# AutoTunerV2.net
KiCad netlist of a schematic drawn in EAGLE
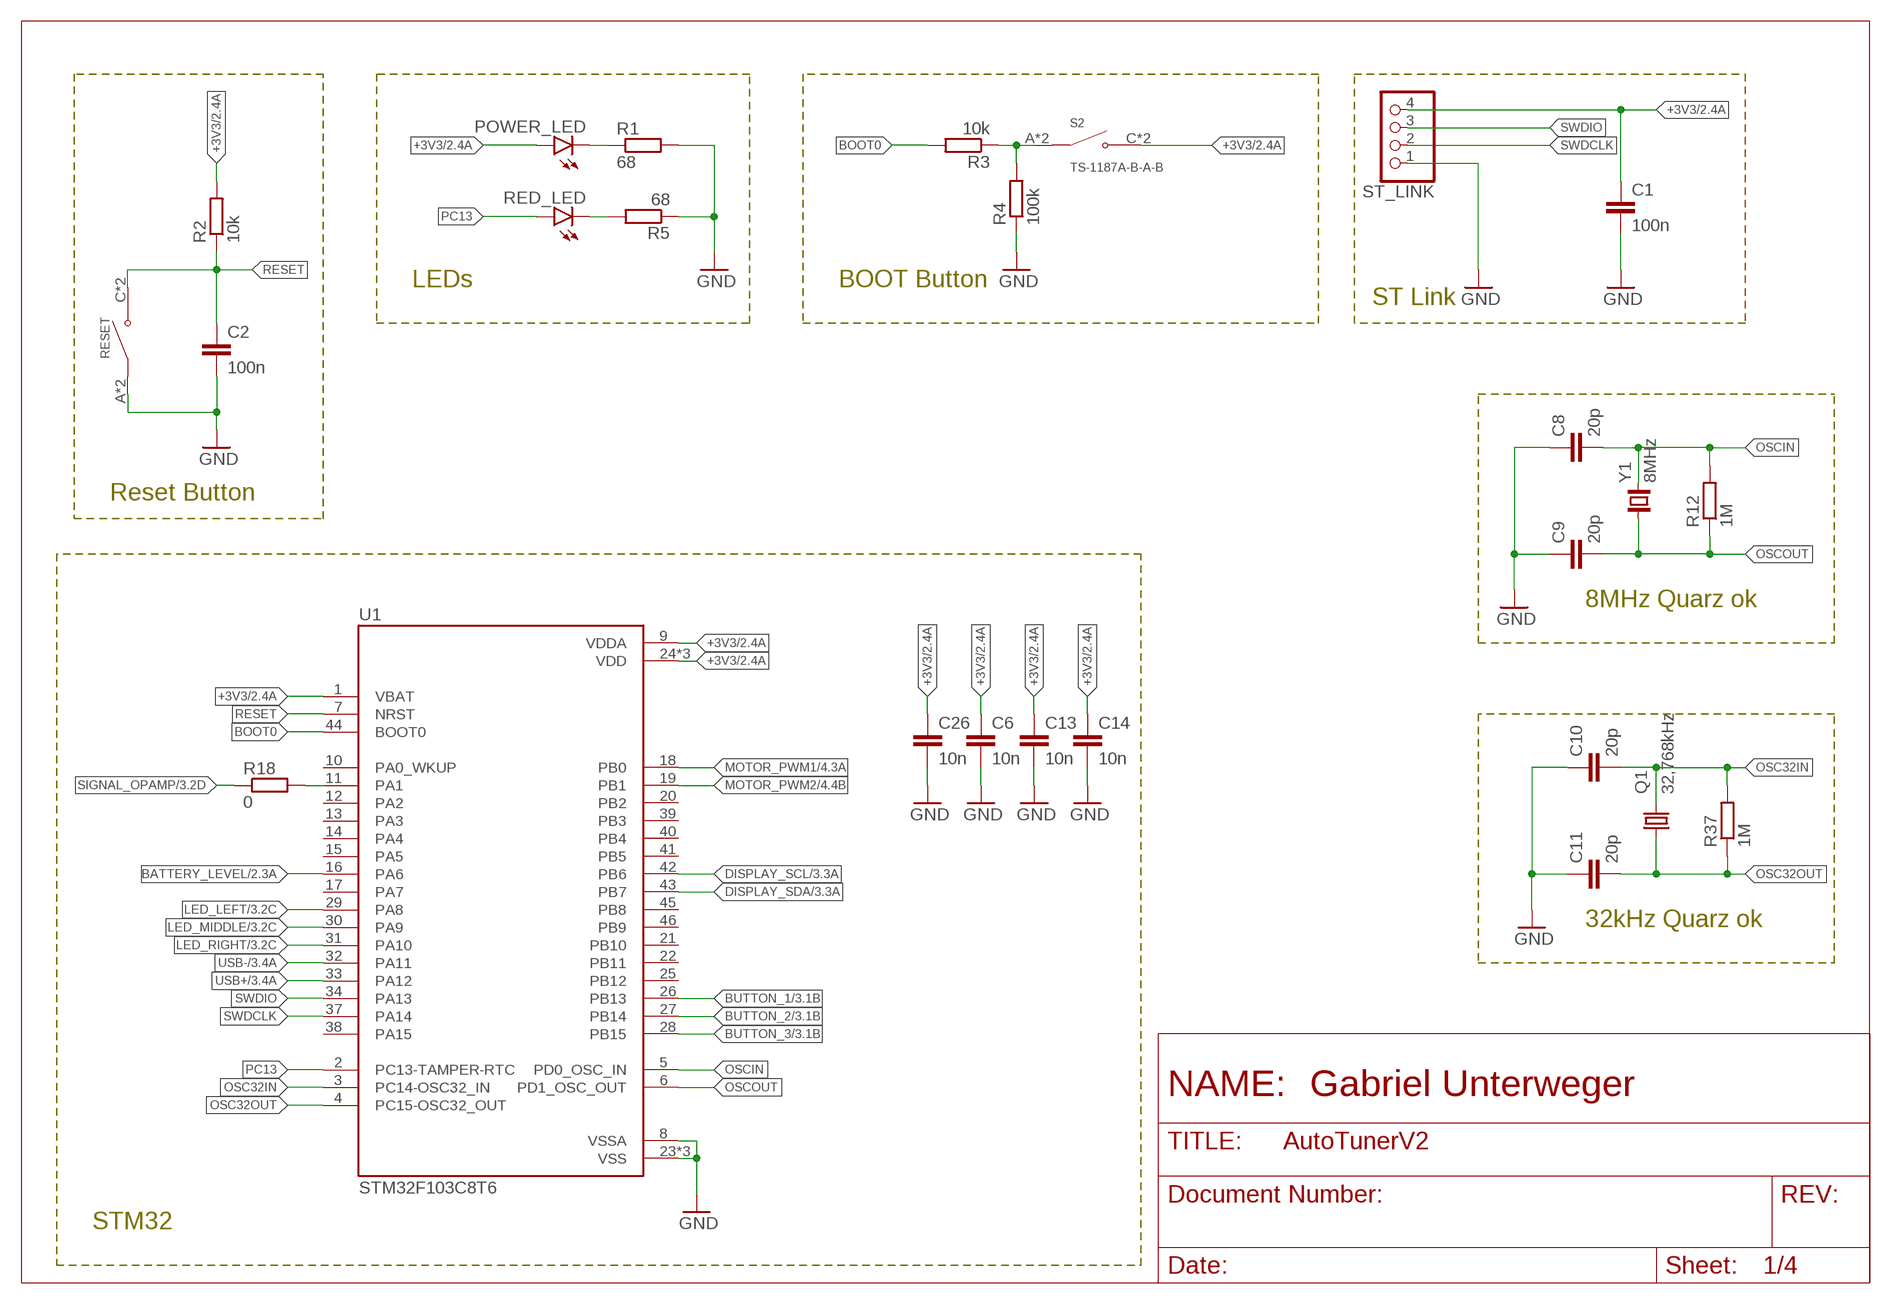
[diagram p0: schematic, sheet 1]
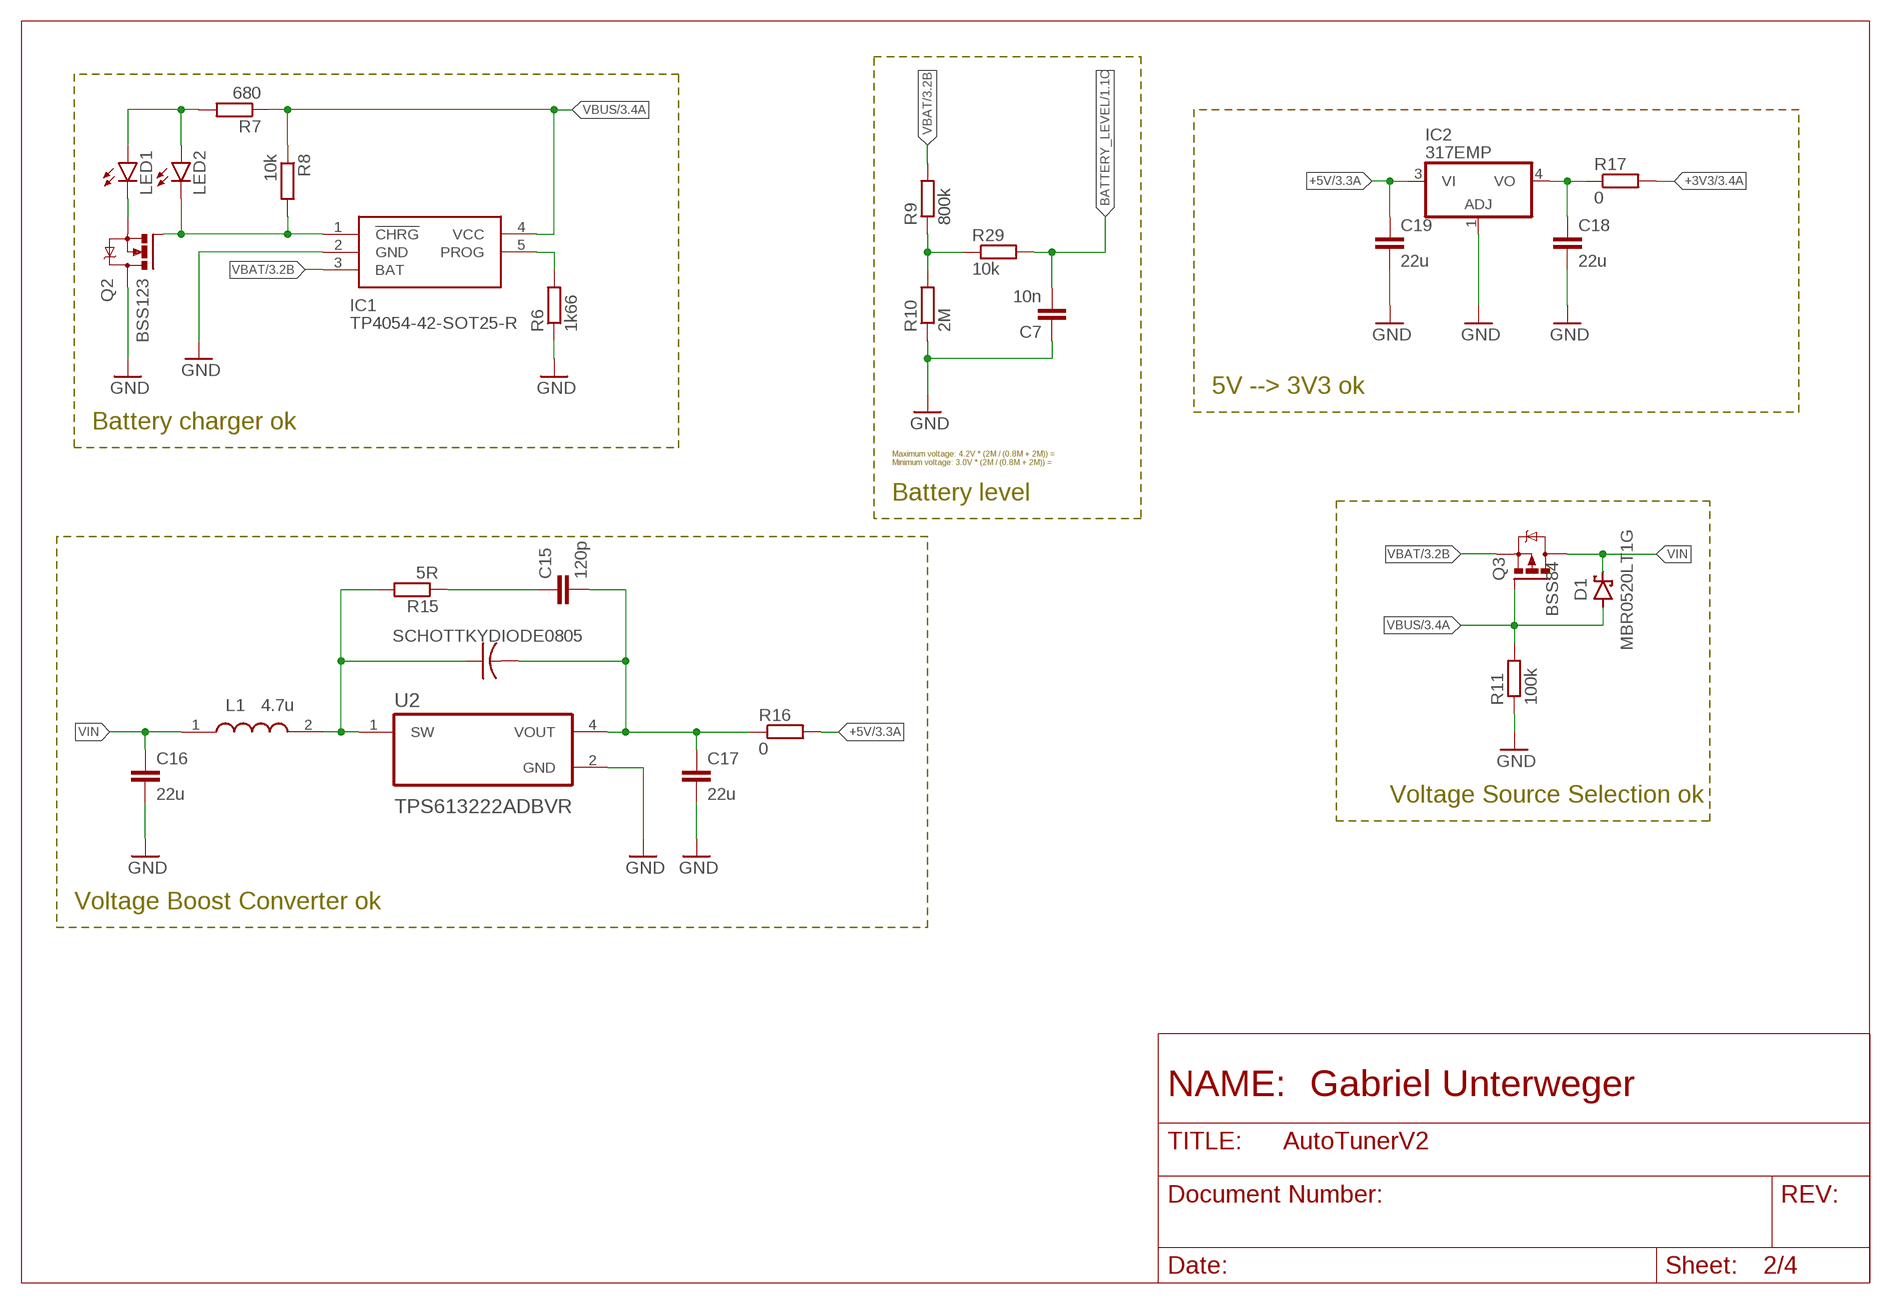
[diagram p1: schematic, sheet 2]
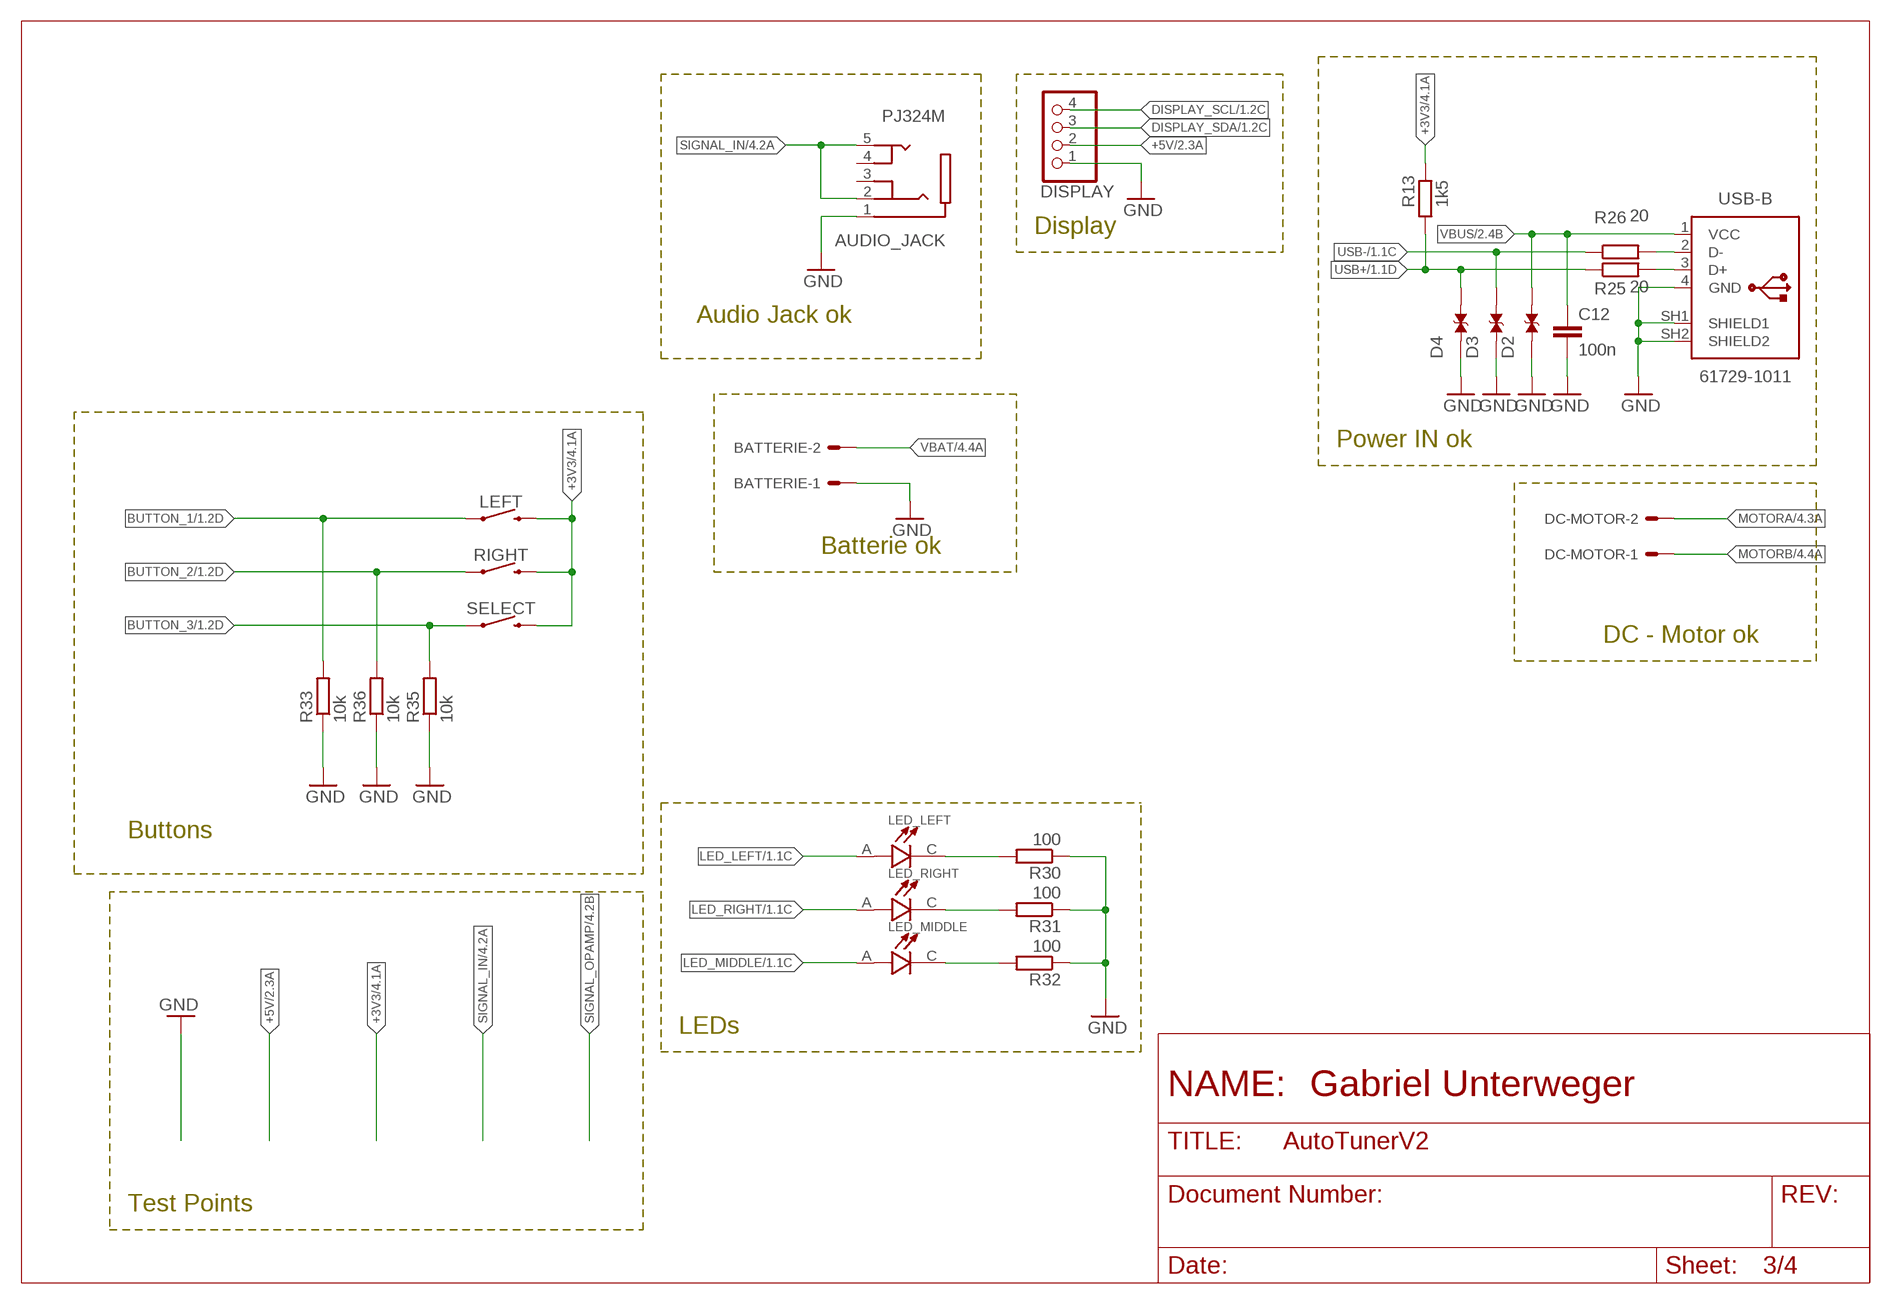
[diagram p2: schematic, sheet 3]
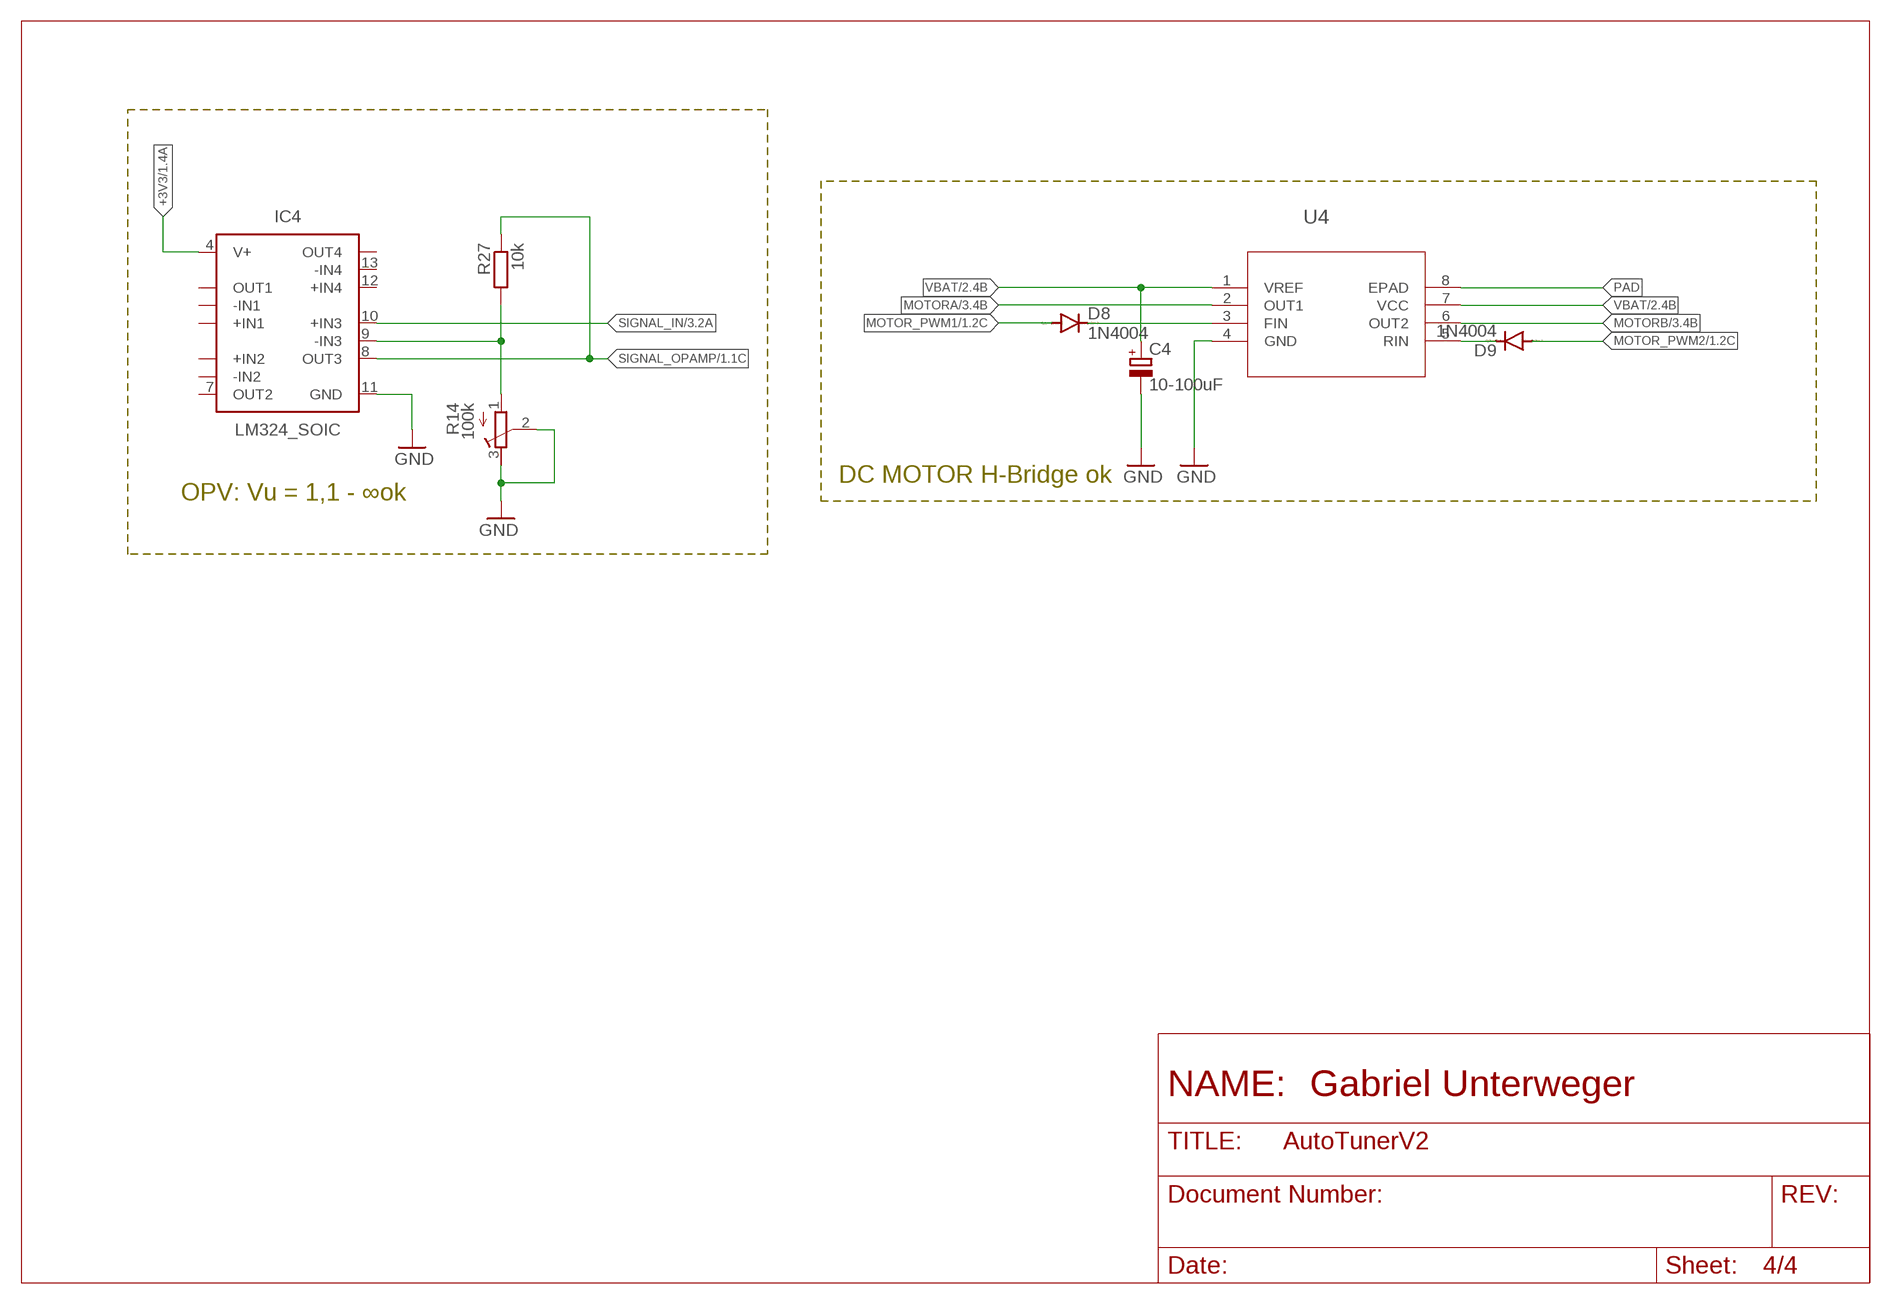
[diagram p3: schematic, sheet 4]

(export (version "E")
  (design (tool "Eeschema 10.0.6"))
  (components
    (comp (ref "C7")
      (value "10n")
      (footprint "eagle-import:C0805")
      (libsource (lib "eagle-import") (part "C-EUC0805"))
    )
    (comp (ref "C15")
      (value "120p")
      (footprint "eagle-import:C0805")
      (libsource (lib "eagle-import") (part "C-EUC0805"))
    )
    (comp (ref "C16")
      (value "22u")
      (footprint "eagle-import:C1206")
      (fields (field (name "LCSC_PART") "C5672"))
      (libsource (lib "eagle-import") (part "C-EUC1206"))
    )
    (comp (ref "C17")
      (value "22u")
      (footprint "eagle-import:C1206")
      (fields (field (name "LCSC_PART") "C5672"))
      (libsource (lib "eagle-import") (part "C-EUC1206"))
    )
    (comp (ref "C18")
      (value "22u")
      (footprint "eagle-import:C1206")
      (fields (field (name "LCSC_PART") "C5672"))
      (libsource (lib "eagle-import") (part "C-EUC1206"))
    )
    (comp (ref "C19")
      (value "22u")
      (footprint "eagle-import:C1206")
      (fields (field (name "LCSC_PART") "C5672"))
      (libsource (lib "eagle-import") (part "C-EUC1206"))
    )
    (comp (ref "D1")
      (value "MBR0520LT1G")
      (footprint "eagle-import:SODFL3718X115")
      (fields (field (name "MANUFACTURER") "ON Semiconductor") (field (name "LCSC_PART") "C191023"))
      (libsource (lib "eagle-import") (part "SCHOTTKY_DO-219MBR0520LT1G"))
    )
    (comp (ref "IC1")
      (value "TP4054-42-SOT25-R")
      (footprint "eagle-import:SOT95P280X100-5N")
      (fields (field (name "LCSC_PART") "C32574"))
      (libsource (lib "eagle-import") (part "TP4054-42-SOT25-R"))
    )
    (comp (ref "IC2")
      (value "317EMP")
      (footprint "eagle-import:SOT223")
      (fields (field (name "LCSC_PART") "C6186"))
      (libsource (lib "eagle-import") (part "317EMP"))
    )
    (comp (ref "L1")
      (value "4.7u")
      (footprint "eagle-import:DFE2HCAH1R0MJ0L")
      (fields
        (field (name "ARROW_PART_NUMBER") "DFE252012P-4R7M=P2")
        (field (name "MOUSER_PART_NUMBER") "81-DFE252012P-4R7MP2")
        (field (name "LCSC_PART") "C391306")
      )
      (libsource (lib "eagle-import") (part "DFE252012P-4R7M=P2"))
    )
    (comp (ref "LED1")
      (value "LEDCHIPLED_0805")
      (footprint "eagle-import:CHIPLED_0805")
      (fields (field (name "LCSC_PART") "C2297"))
      (libsource (lib "eagle-import") (part "LEDCHIPLED_0805"))
    )
    (comp (ref "LED2")
      (value "LEDCHIPLED_0805")
      (footprint "eagle-import:CHIPLED_0805")
      (fields (field (name "LCSC_PART") "C84256"))
      (libsource (lib "eagle-import") (part "LEDCHIPLED_0805"))
    )
    (comp (ref "Q2")
      (value "BSS123")
      (footprint "eagle-import:SOT23")
      (fields
        (field (name "MANUFACTURER") "ON Semiconductor")
        (field (name "MPN") "BSS123L")
        (field (name "LCSC_PART") "C20917")
      )
      (libsource (lib "eagle-import") (part "NMOSFET__SOT23-GSDBSS123"))
    )
    (comp (ref "Q3")
      (value "BSS84")
      (footprint "eagle-import:SOT23")
      (fields (field (name "MANUFACTURER") "ON Semiconductor"))
      (libsource (lib "eagle-import") (part "PMOSFET__SOT23-GSDBSS84"))
    )
    (comp (ref "R6")
      (value "1k66")
      (footprint "eagle-import:R0805")
      (libsource (lib "eagle-import") (part "R-EU_R0805"))
    )
    (comp (ref "R7")
      (value "680")
      (footprint "eagle-import:R0805")
      (libsource (lib "eagle-import") (part "R-EU_R0805"))
    )
    (comp (ref "R8")
      (value "10k")
      (footprint "eagle-import:R0805")
      (libsource (lib "eagle-import") (part "R-EU_R0805"))
    )
    (comp (ref "R9")
      (value "800k")
      (footprint "eagle-import:R0805")
      (libsource (lib "eagle-import") (part "R-EU_R0805"))
    )
    (comp (ref "R10")
      (value "2M")
      (footprint "eagle-import:R0805")
      (libsource (lib "eagle-import") (part "R-EU_R0805"))
    )
    (comp (ref "R11")
      (value "100k")
      (footprint "eagle-import:R0805")
      (libsource (lib "eagle-import") (part "R-EU_R0805"))
    )
    (comp (ref "R15")
      (value "5R")
      (footprint "eagle-import:R0805")
      (libsource (lib "eagle-import") (part "R-EU_R0805"))
    )
    (comp (ref "R16")
      (value "0")
      (footprint "eagle-import:R0805")
      (libsource (lib "eagle-import") (part "R-EU_R0805"))
    )
    (comp (ref "R17")
      (value "0")
      (footprint "eagle-import:R0805")
      (libsource (lib "eagle-import") (part "R-EU_R0805"))
    )
    (comp (ref "R29")
      (value "10k")
      (footprint "eagle-import:R0805")
      (libsource (lib "eagle-import") (part "R-EU_R0805"))
    )
    (comp (ref "SCHOTTKYDIODE0805")
      (value "C-USC0805")
      (footprint "eagle-import:C0805")
      (libsource (lib "eagle-import") (part "C-USC0805"))
    )
    (comp (ref "U2")
      (value "TPS613222ADBVR")
      (footprint "eagle-import:SOT95P280X145-5N")
      (fields (field (name "MF") "Texas Instruments") (field (name "LCSC_PART") "C2071163"))
      (libsource (lib "eagle-import") (part "TPS613222ADBVR"))
    )
    (comp (ref "AUDIO_JACK")
      (value "PJ324M")
      (footprint "eagle-import:WENZHOU_PJ324M")
      (fields (field (name "MF") "Wenzhou QingPu Electronics Co.Ltd"))
      (libsource (lib "eagle-import") (part "PJ324M"))
    )
    (comp (ref "BATTERIE")
      (value "22-27-2021-02")
      (footprint "eagle-import:6410-02")
      (fields (field (name "MF") "MOLEX"))
      (libsource (lib "eagle-import") (part "22-?-0227-2021"))
    )
    (comp (ref "C12")
      (value "100n")
      (footprint "eagle-import:C0805")
      (libsource (lib "eagle-import") (part "C-EUC0805"))
    )
    (comp (ref "D2")
      (value "TESD5V0L1UC_RJG")
      (footprint "eagle-import:DIO_TESD5V0L1UC_RJG")
      (fields
        (field (name "MF") "Taiwan Semiconductor Corporation")
        (field (name "MP") "TESD5V0L1UC RJG")
        (field (name "LCSC_PART") "C7420372")
      )
      (libsource (lib "eagle-import") (part "TESD5V0L1UC_RJG"))
    )
    (comp (ref "D3")
      (value "TESD5V0L1UC_RJG")
      (footprint "eagle-import:DIO_TESD5V0L1UC_RJG")
      (fields
        (field (name "MF") "Taiwan Semiconductor Corporation")
        (field (name "MP") "TESD5V0L1UC RJG")
        (field (name "LCSC_PART") "C7420372")
      )
      (libsource (lib "eagle-import") (part "TESD5V0L1UC_RJG"))
    )
    (comp (ref "D4")
      (value "TESD5V0L1UC_RJG")
      (footprint "eagle-import:DIO_TESD5V0L1UC_RJG")
      (fields
        (field (name "MF") "Taiwan Semiconductor Corporation")
        (field (name "MP") "TESD5V0L1UC RJG")
        (field (name "LCSC_PART") "C7420372")
      )
      (libsource (lib "eagle-import") (part "TESD5V0L1UC_RJG"))
    )
    (comp (ref "DC-MOTOR")
      (value "22-27-2021-02")
      (footprint "eagle-import:6410-02")
      (fields (field (name "MF") "MOLEX"))
      (libsource (lib "eagle-import") (part "22-?-0227-2021"))
    )
    (comp (ref "DISPLAY")
      (value "PINHD-1X4")
      (footprint "eagle-import:1X04")
      (libsource (lib "eagle-import") (part "PINHD-1X4"))
    )
    (comp (ref "LED_LEFT")
      (value "L-53GD")
      (footprint "eagle-import:LEDRD254W50D500H1060")
      (fields (field (name "MF") "Kingbright"))
      (libsource (lib "eagle-import") (part "L-53GD"))
    )
    (comp (ref "LED_MIDDLE")
      (value "L-53GD")
      (footprint "eagle-import:LEDRD254W50D500H1060")
      (fields (field (name "MF") "Kingbright"))
      (libsource (lib "eagle-import") (part "L-53GD"))
    )
    (comp (ref "LED_RIGHT")
      (value "L-53GD")
      (footprint "eagle-import:LEDRD254W50D500H1060")
      (fields (field (name "MF") "Kingbright"))
      (libsource (lib "eagle-import") (part "L-53GD"))
    )
    (comp (ref "LEFT")
      (value "MOMENTARY-SWITCH-SPST-PTH-12MM")
      (footprint "eagle-import:TACTILE_SWITCH_PTH_12MM")
      (libsource (lib "eagle-import") (part "MOMENTARY-SWITCH-SPST-PTH-12MM"))
    )
    (comp (ref "R13")
      (value "1k5")
      (footprint "eagle-import:R0805")
      (libsource (lib "eagle-import") (part "R-EU_R0805"))
    )
    (comp (ref "R25")
      (value "20")
      (footprint "eagle-import:R0805")
      (libsource (lib "eagle-import") (part "R-EU_R0805"))
    )
    (comp (ref "R26")
      (value "20")
      (footprint "eagle-import:R0805")
      (libsource (lib "eagle-import") (part "R-EU_R0805"))
    )
    (comp (ref "R30")
      (value "100")
      (footprint "eagle-import:R0805")
      (libsource (lib "eagle-import") (part "R-EU_R0805"))
    )
    (comp (ref "R31")
      (value "100")
      (footprint "eagle-import:R0805")
      (libsource (lib "eagle-import") (part "R-EU_R0805"))
    )
    (comp (ref "R32")
      (value "100")
      (footprint "eagle-import:R0805")
      (libsource (lib "eagle-import") (part "R-EU_R0805"))
    )
    (comp (ref "R33")
      (value "10k")
      (footprint "eagle-import:R0805")
      (libsource (lib "eagle-import") (part "R-EU_R0805"))
    )
    (comp (ref "R35")
      (value "10k")
      (footprint "eagle-import:R0805")
      (libsource (lib "eagle-import") (part "R-EU_R0805"))
    )
    (comp (ref "R36")
      (value "10k")
      (footprint "eagle-import:R0805")
      (libsource (lib "eagle-import") (part "R-EU_R0805"))
    )
    (comp (ref "RIGHT")
      (value "MOMENTARY-SWITCH-SPST-PTH-12MM")
      (footprint "eagle-import:TACTILE_SWITCH_PTH_12MM")
      (libsource (lib "eagle-import") (part "MOMENTARY-SWITCH-SPST-PTH-12MM"))
    )
    (comp (ref "SELECT")
      (value "MOMENTARY-SWITCH-SPST-PTH-12MM")
      (footprint "eagle-import:TACTILE_SWITCH_PTH_12MM")
      (libsource (lib "eagle-import") (part "MOMENTARY-SWITCH-SPST-PTH-12MM"))
    )
    (comp (ref "USB-B")
      (value "61729-1011")
      (footprint "eagle-import:61729-1011BLF")
      (fields (field (name "MANUFACTURER") "Amphenol ICC (FCI)") (field (name "MPN") "61729-1011BLF"))
      (libsource (lib "eagle-import") (part "61729-1011"))
    )
    (comp (ref "C1")
      (value "100n")
      (footprint "eagle-import:C0805")
      (libsource (lib "eagle-import") (part "C-EUC0805"))
    )
    (comp (ref "C2")
      (value "100n")
      (footprint "eagle-import:C0805")
      (libsource (lib "eagle-import") (part "C-EUC0805"))
    )
    (comp (ref "C6")
      (value "10n")
      (footprint "eagle-import:C0805")
      (libsource (lib "eagle-import") (part "C-EUC0805"))
    )
    (comp (ref "C8")
      (value "20p")
      (footprint "eagle-import:C0805")
      (libsource (lib "eagle-import") (part "C-EUC0805"))
    )
    (comp (ref "C9")
      (value "20p")
      (footprint "eagle-import:C0805")
      (libsource (lib "eagle-import") (part "C-EUC0805"))
    )
    (comp (ref "C10")
      (value "20p")
      (footprint "eagle-import:C0805")
      (libsource (lib "eagle-import") (part "C-EUC0805"))
    )
    (comp (ref "C11")
      (value "20p")
      (footprint "eagle-import:C0805")
      (libsource (lib "eagle-import") (part "C-EUC0805"))
    )
    (comp (ref "C13")
      (value "10n")
      (footprint "eagle-import:C0805")
      (libsource (lib "eagle-import") (part "C-EUC0805"))
    )
    (comp (ref "C14")
      (value "10n")
      (footprint "eagle-import:C0805")
      (libsource (lib "eagle-import") (part "C-EUC0805"))
    )
    (comp (ref "C26")
      (value "10n")
      (footprint "eagle-import:C0805")
      (libsource (lib "eagle-import") (part "C-EUC0805"))
    )
    (comp (ref "POWER_LED")
      (value "LEDCHIPLED_0805")
      (footprint "eagle-import:CHIPLED_0805")
      (fields (field (name "LCSC_PART") "C2297"))
      (libsource (lib "eagle-import") (part "LEDCHIPLED_0805"))
    )
    (comp (ref "Q1")
      (value "32,768kHz")
      (footprint "eagle-import:3.2X1.5")
      (fields (field (name "LCSC_PART") "C32346"))
      (libsource (lib "eagle-import") (part "KX-327-NHF"))
    )
    (comp (ref "R1")
      (value "68")
      (footprint "eagle-import:R0805")
      (libsource (lib "eagle-import") (part "R-EU_R0805"))
    )
    (comp (ref "R2")
      (value "10k")
      (footprint "eagle-import:R0805")
      (libsource (lib "eagle-import") (part "R-EU_R0805"))
    )
    (comp (ref "R3")
      (value "10k")
      (footprint "eagle-import:R0805")
      (libsource (lib "eagle-import") (part "R-EU_R0805"))
    )
    (comp (ref "R4")
      (value "100k")
      (footprint "eagle-import:R0805")
      (libsource (lib "eagle-import") (part "R-EU_R0805"))
    )
    (comp (ref "R5")
      (value "68")
      (footprint "eagle-import:R0805")
      (libsource (lib "eagle-import") (part "R-EU_R0805"))
    )
    (comp (ref "R12")
      (value "1M")
      (footprint "eagle-import:R0805")
      (libsource (lib "eagle-import") (part "R-EU_R0805"))
    )
    (comp (ref "R18")
      (value "0")
      (footprint "eagle-import:R0805")
      (libsource (lib "eagle-import") (part "R-EU_R0805"))
    )
    (comp (ref "R37")
      (value "1M")
      (footprint "eagle-import:R0805")
      (libsource (lib "eagle-import") (part "R-EU_R0805"))
    )
    (comp (ref "RED_LED")
      (value "LEDCHIPLED_0805")
      (footprint "eagle-import:CHIPLED_0805")
      (fields (field (name "LCSC_PART") "C84256"))
      (libsource (lib "eagle-import") (part "LEDCHIPLED_0805"))
    )
    (comp (ref "RESET")
      (value "TS-1187A-B-A-B")
      (footprint "eagle-import:SW_TS-1187A-B-A-B")
      (fields (field (name "MF") "XKB Industrial Precision") (field (name "LCSC_PART") "C318884"))
      (libsource (lib "eagle-import") (part "TS-1187A-B-A-B"))
    )
    (comp (ref "S2")
      (value "TS-1187A-B-A-B")
      (footprint "eagle-import:SW_TS-1187A-B-A-B")
      (fields (field (name "MF") "XKB Industrial Precision") (field (name "LCSC_PART") "C318884"))
      (libsource (lib "eagle-import") (part "TS-1187A-B-A-B"))
    )
    (comp (ref "ST_LINK")
      (value "PINHD-1X4")
      (footprint "eagle-import:1X04")
      (libsource (lib "eagle-import") (part "PINHD-1X4"))
    )
    (comp (ref "U1")
      (value "STM32F103C8T6")
      (footprint "eagle-import:QFP50P900X900X160-48N")
      (fields (field (name "MF") "STMicroelectronics") (field (name "LCSC_PART") "C8734"))
      (libsource (lib "eagle-import") (part "STM32F103C8T6"))
    )
    (comp (ref "Y1")
      (value "8MHz")
      (footprint "eagle-import:CRYSTAL_2-SMD-5X3")
      (fields (field (name "LCSC_PART") "C115962"))
      (libsource (lib "eagle-import") (part "CRYSTAL_NX5032GA"))
    )
    (comp (ref "C4")
      (value "10-100uF")
      (footprint "eagle-import:B45181A")
      (libsource (lib "eagle-import") (part "CPOL-EUB45181A"))
    )
    (comp (ref "D8")
      (value "1N4004")
      (footprint "eagle-import:DO41-10")
      (libsource (lib "eagle-import") (part "1N4004"))
    )
    (comp (ref "D9")
      (value "1N4004")
      (footprint "eagle-import:DO41-10")
      (libsource (lib "eagle-import") (part "1N4004"))
    )
    (comp (ref "IC4")
      (value "LM324_SOIC")
      (footprint "eagle-import:SOIC127P600X175-14N")
      (fields (field (name "MANUFACTURER") "Generic") (field (name "LCSC_PART") "C71035"))
      (libsource (lib "eagle-import") (part "LM324_SOIC"))
    )
    (comp (ref "R14")
      (value "100k")
      (footprint "eagle-import:RTRIM64Y")
      (libsource (lib "eagle-import") (part "R-TRIMM64Y"))
    )
    (comp (ref "R27")
      (value "10k")
      (footprint "eagle-import:R0805")
      (libsource (lib "eagle-import") (part "R-EU_R0805"))
    )
    (comp (ref "U4")
      (value "BD6222HFP-TRHRP7_ROM-M")
      (footprint "eagle-import:HRP7_ROM-M")
      (fields
        (field (name "MANUFACTURER_PART_NUMBER") "BD6222HFP-TR")
        (field (name "COPYRIGHT") "Copyright (C) 2022 Ultra Librarian. All rights reserved.")
      )
      (libsource (lib "eagle-import") (part "BD6222HFP-TRHRP7_ROM-M"))
    )
  )
  (nets
    (net (code "1") (name "+3V3") (class "Default")
      (node (ref "C1") (pin "1") (pinfunction "1_1") (pintype "passive"))
      (node (ref "C13") (pin "1") (pinfunction "1_1") (pintype "passive"))
      (node (ref "C14") (pin "1") (pinfunction "1_1") (pintype "passive"))
      (node (ref "C26") (pin "1") (pinfunction "1_1") (pintype "passive"))
      (node (ref "C6") (pin "1") (pinfunction "1_1") (pintype "passive"))
      (node (ref "IC4") (pin "4") (pinfunction "V+_4") (pintype "passive"))
      (node (ref "LEFT") (pin "3") (pinfunction "2_3") (pintype "passive"))
      (node (ref "POWER_LED") (pin "A") (pinfunction "A_A") (pintype "passive"))
      (node (ref "R13") (pin "2") (pinfunction "2_2") (pintype "passive"))
      (node (ref "R17") (pin "2") (pinfunction "2_2") (pintype "passive"))
      (node (ref "R2") (pin "2") (pinfunction "2_2") (pintype "passive"))
      (node (ref "RIGHT") (pin "3") (pinfunction "2_3") (pintype "passive"))
      (node (ref "S2") (pin "C") (pinfunction "NO_C") (pintype "passive"))
      (node (ref "S2") (pin "D") (pinfunction "NO_D") (pintype "passive"))
      (node (ref "SELECT") (pin "3") (pinfunction "2_3") (pintype "passive"))
      (node (ref "ST_LINK") (pin "4") (pinfunction "4_4") (pintype "passive"))
      (node (ref "U1") (pin "1") (pinfunction "VBAT_1") (pintype "bidirectional"))
      (node (ref "U1") (pin "24") (pinfunction "VDD_24") (pintype "power_in"))
      (node (ref "U1") (pin "36") (pinfunction "VDD_36") (pintype "power_in"))
      (node (ref "U1") (pin "48") (pinfunction "VDD_48") (pintype "power_in"))
      (node (ref "U1") (pin "9") (pinfunction "VDDA_9") (pintype "power_in"))
    )
    (net (code "2") (name "+5V") (class "Default")
      (node (ref "C19") (pin "1") (pinfunction "1_1") (pintype "passive"))
      (node (ref "DISPLAY") (pin "2") (pinfunction "2_2") (pintype "passive"))
      (node (ref "IC2") (pin "3") (pinfunction "VI_3") (pintype "input"))
      (node (ref "R16") (pin "2") (pinfunction "2_2") (pintype "passive"))
    )
    (net (code "3") (name "BATTERY_LEVEL") (class "Default")
      (node (ref "C7") (pin "2") (pinfunction "2_2") (pintype "passive"))
      (node (ref "R29") (pin "2") (pinfunction "2_2") (pintype "passive"))
      (node (ref "U1") (pin "16") (pinfunction "PA6_16") (pintype "bidirectional"))
    )
    (net (code "4") (name "BOOT0") (class "Default")
      (node (ref "R3") (pin "2") (pinfunction "2_2") (pintype "passive"))
      (node (ref "U1") (pin "44") (pinfunction "BOOT0_44") (pintype "input"))
    )
    (net (code "5") (name "BUTTON_1") (class "Default")
      (node (ref "LEFT") (pin "1") (pinfunction "1_1") (pintype "passive"))
      (node (ref "R33") (pin "2") (pinfunction "2_2") (pintype "passive"))
      (node (ref "U1") (pin "26") (pinfunction "PB13_26") (pintype "bidirectional"))
    )
    (net (code "6") (name "BUTTON_2") (class "Default")
      (node (ref "R36") (pin "2") (pinfunction "2_2") (pintype "passive"))
      (node (ref "RIGHT") (pin "1") (pinfunction "1_1") (pintype "passive"))
      (node (ref "U1") (pin "27") (pinfunction "PB14_27") (pintype "bidirectional"))
    )
    (net (code "7") (name "BUTTON_3") (class "Default")
      (node (ref "R35") (pin "2") (pinfunction "2_2") (pintype "passive"))
      (node (ref "SELECT") (pin "1") (pinfunction "1_1") (pintype "passive"))
      (node (ref "U1") (pin "28") (pinfunction "PB15_28") (pintype "bidirectional"))
    )
    (net (code "8") (name "DISPLAY_SCL") (class "Default")
      (node (ref "DISPLAY") (pin "4") (pinfunction "4_4") (pintype "passive"))
      (node (ref "U1") (pin "42") (pinfunction "PB6_42") (pintype "bidirectional"))
    )
    (net (code "9") (name "DISPLAY_SDA") (class "Default")
      (node (ref "DISPLAY") (pin "3") (pinfunction "3_3") (pintype "passive"))
      (node (ref "U1") (pin "43") (pinfunction "PB7_43") (pintype "bidirectional"))
    )
    (net (code "10") (name "GND") (class "Default")
      (node (ref "AUDIO_JACK") (pin "1") (pinfunction "SLEEVE_1") (pintype "passive"))
      (node (ref "BATTERIE") (pin "1") (pinfunction "S_1") (pintype "passive"))
      (node (ref "C1") (pin "2") (pinfunction "2_2") (pintype "passive"))
      (node (ref "C10") (pin "1") (pinfunction "1_1") (pintype "passive"))
      (node (ref "C11") (pin "1") (pinfunction "1_1") (pintype "passive"))
      (node (ref "C12") (pin "2") (pinfunction "2_2") (pintype "passive"))
      (node (ref "C13") (pin "2") (pinfunction "2_2") (pintype "passive"))
      (node (ref "C14") (pin "2") (pinfunction "2_2") (pintype "passive"))
      (node (ref "C16") (pin "2") (pinfunction "2_2") (pintype "passive"))
      (node (ref "C17") (pin "2") (pinfunction "2_2") (pintype "passive"))
      (node (ref "C18") (pin "2") (pinfunction "2_2") (pintype "passive"))
      (node (ref "C19") (pin "2") (pinfunction "2_2") (pintype "passive"))
      (node (ref "C2") (pin "2") (pinfunction "2_2") (pintype "passive"))
      (node (ref "C26") (pin "2") (pinfunction "2_2") (pintype "passive"))
      (node (ref "C4") (pin "-") (pinfunction "-_-") (pintype "passive"))
      (node (ref "C6") (pin "2") (pinfunction "2_2") (pintype "passive"))
      (node (ref "C7") (pin "1") (pinfunction "1_1") (pintype "passive"))
      (node (ref "C8") (pin "1") (pinfunction "1_1") (pintype "passive"))
      (node (ref "C9") (pin "1") (pinfunction "1_1") (pintype "passive"))
      (node (ref "D2") (pin "1") (pinfunction "1_1") (pintype "passive"))
      (node (ref "D3") (pin "1") (pinfunction "1_1") (pintype "passive"))
      (node (ref "D4") (pin "1") (pinfunction "1_1") (pintype "passive"))
      (node (ref "DISPLAY") (pin "1") (pinfunction "1_1") (pintype "passive"))
      (node (ref "IC1") (pin "2") (pinfunction "GND_2") (pintype "bidirectional"))
      (node (ref "IC2") (pin "1") (pinfunction "ADJ_1") (pintype "input"))
      (node (ref "IC4") (pin "11") (pinfunction "GND_11") (pintype "passive"))
      (node (ref "Q2") (pin "3") (pinfunction "D_3") (pintype "passive"))
      (node (ref "R1") (pin "2") (pinfunction "2_2") (pintype "passive"))
      (node (ref "R10") (pin "1") (pinfunction "1_1") (pintype "passive"))
      (node (ref "R11") (pin "1") (pinfunction "1_1") (pintype "passive"))
      (node (ref "R14") (pin "2") (pinfunction "S_2") (pintype "passive"))
      (node (ref "R14") (pin "3") (pinfunction "E_3") (pintype "passive"))
      (node (ref "R30") (pin "1") (pinfunction "1_1") (pintype "passive"))
      (node (ref "R31") (pin "1") (pinfunction "1_1") (pintype "passive"))
      (node (ref "R32") (pin "1") (pinfunction "1_1") (pintype "passive"))
      (node (ref "R33") (pin "1") (pinfunction "1_1") (pintype "passive"))
      (node (ref "R35") (pin "1") (pinfunction "1_1") (pintype "passive"))
      (node (ref "R36") (pin "1") (pinfunction "1_1") (pintype "passive"))
      (node (ref "R4") (pin "1") (pinfunction "1_1") (pintype "passive"))
      (node (ref "R5") (pin "1") (pinfunction "1_1") (pintype "passive"))
      (node (ref "R6") (pin "1") (pinfunction "1_1") (pintype "passive"))
      (node (ref "RESET") (pin "A") (pinfunction "COM_A") (pintype "passive"))
      (node (ref "RESET") (pin "B") (pinfunction "COM_B") (pintype "passive"))
      (node (ref "ST_LINK") (pin "1") (pinfunction "1_1") (pintype "passive"))
      (node (ref "U1") (pin "23") (pinfunction "VSS_23") (pintype "power_in"))
      (node (ref "U1") (pin "35") (pinfunction "VSS_35") (pintype "power_in"))
      (node (ref "U1") (pin "47") (pinfunction "VSS_47") (pintype "power_in"))
      (node (ref "U1") (pin "8") (pinfunction "VSSA_8") (pintype "power_in"))
      (node (ref "U2") (pin "2") (pinfunction "GND_2") (pintype "power_in"))
      (node (ref "U4") (pin "4") (pinfunction "GND_4") (pintype "passive"))
      (node (ref "USB-B") (pin "4") (pinfunction "GND_4") (pintype "power_in"))
      (node (ref "USB-B") (pin "SH1") (pinfunction "SHIELD1_SH1") (pintype "power_in"))
      (node (ref "USB-B") (pin "SH2") (pinfunction "SHIELD2_SH2") (pintype "power_in"))
    )
    (net (code "11") (name "LED_LEFT") (class "Default")
      (node (ref "LED_LEFT") (pin "A") (pinfunction "A_A") (pintype "passive"))
      (node (ref "U1") (pin "29") (pinfunction "PA8_29") (pintype "bidirectional"))
    )
    (net (code "12") (name "LED_MIDDLE") (class "Default")
      (node (ref "LED_MIDDLE") (pin "A") (pinfunction "A_A") (pintype "passive"))
      (node (ref "U1") (pin "30") (pinfunction "PA9_30") (pintype "bidirectional"))
    )
    (net (code "13") (name "LED_RIGHT") (class "Default")
      (node (ref "LED_RIGHT") (pin "A") (pinfunction "A_A") (pintype "passive"))
      (node (ref "U1") (pin "31") (pinfunction "PA10_31") (pintype "bidirectional"))
    )
    (net (code "14") (name "MOTORA") (class "Default")
      (node (ref "DC-MOTOR") (pin "2") (pinfunction "S_2") (pintype "passive"))
      (node (ref "U4") (pin "2") (pinfunction "OUT1_2") (pintype "output"))
    )
    (net (code "15") (name "MOTORB") (class "Default")
      (node (ref "DC-MOTOR") (pin "1") (pinfunction "S_1") (pintype "passive"))
      (node (ref "U4") (pin "6") (pinfunction "OUT2_6") (pintype "output"))
    )
    (net (code "16") (name "MOTOR_PWM1") (class "Default")
      (node (ref "D8") (pin "A") (pinfunction "A_A") (pintype "passive"))
      (node (ref "U1") (pin "18") (pinfunction "PB0_18") (pintype "bidirectional"))
    )
    (net (code "17") (name "MOTOR_PWM2") (class "Default")
      (node (ref "D9") (pin "A") (pinfunction "A_A") (pintype "passive"))
      (node (ref "U1") (pin "19") (pinfunction "PB1_19") (pintype "bidirectional"))
    )
    (net (code "18") (name "Net-(C15-Pad1)") (class "Default")
      (node (ref "C15") (pin "1") (pinfunction "1_1") (pintype "passive"))
      (node (ref "R15") (pin "1") (pinfunction "1_1") (pintype "passive"))
    )
    (net (code "19") (name "Net-(IC1-PROG)") (class "Default")
      (node (ref "IC1") (pin "5") (pinfunction "PROG_5") (pintype "bidirectional"))
      (node (ref "R6") (pin "2") (pinfunction "2_2") (pintype "passive"))
    )
    (net (code "20") (name "Net-(IC1-~{CHRG})") (class "Default")
      (node (ref "IC1") (pin "1") (pinfunction "~{CHRG}_1") (pintype "bidirectional"))
      (node (ref "LED2") (pin "C") (pinfunction "C_C") (pintype "passive"))
      (node (ref "Q2") (pin "1") (pinfunction "G_1") (pintype "passive"))
      (node (ref "R8") (pin "2") (pinfunction "2_2") (pintype "passive"))
    )
    (net (code "21") (name "Net-(IC2-VO)") (class "Default")
      (node (ref "C18") (pin "1") (pinfunction "1_1") (pintype "passive"))
      (node (ref "IC2") (pin "4") (pinfunction "VO_4") (pintype "passive"))
      (node (ref "R17") (pin "1") (pinfunction "1_1") (pintype "passive"))
    )
    (net (code "22") (name "Net-(IC4--IN3)") (class "Default")
      (node (ref "IC4") (pin "9") (pinfunction "-IN3_9") (pintype "passive"))
      (node (ref "R14") (pin "1") (pinfunction "A_1") (pintype "passive"))
      (node (ref "R27") (pin "2") (pinfunction "2_2") (pintype "passive"))
    )
    (net (code "23") (name "Net-(LED1-PadA)") (class "Default")
      (node (ref "LED1") (pin "A") (pinfunction "A_A") (pintype "passive"))
      (node (ref "LED2") (pin "A") (pinfunction "A_A") (pintype "passive"))
      (node (ref "R7") (pin "2") (pinfunction "2_2") (pintype "passive"))
    )
    (net (code "24") (name "Net-(LED_LEFT-PadC)") (class "Default")
      (node (ref "LED_LEFT") (pin "C") (pinfunction "C_C") (pintype "passive"))
      (node (ref "R30") (pin "2") (pinfunction "2_2") (pintype "passive"))
    )
    (net (code "25") (name "Net-(LED_MIDDLE-PadC)") (class "Default")
      (node (ref "LED_MIDDLE") (pin "C") (pinfunction "C_C") (pintype "passive"))
      (node (ref "R32") (pin "2") (pinfunction "2_2") (pintype "passive"))
    )
    (net (code "26") (name "Net-(LED_RIGHT-PadC)") (class "Default")
      (node (ref "LED_RIGHT") (pin "C") (pinfunction "C_C") (pintype "passive"))
      (node (ref "R31") (pin "2") (pinfunction "2_2") (pintype "passive"))
    )
    (net (code "27") (name "Net-(POWER_LED-PadC)") (class "Default")
      (node (ref "POWER_LED") (pin "C") (pinfunction "C_C") (pintype "passive"))
      (node (ref "R1") (pin "1") (pinfunction "1_1") (pintype "passive"))
    )
    (net (code "28") (name "Net-(Q2-S)") (class "Default")
      (node (ref "LED1") (pin "C") (pinfunction "C_C") (pintype "passive"))
      (node (ref "Q2") (pin "2") (pinfunction "S_2") (pintype "passive"))
    )
    (net (code "29") (name "Net-(R3-Pad1)") (class "Default")
      (node (ref "R3") (pin "1") (pinfunction "1_1") (pintype "passive"))
      (node (ref "R4") (pin "2") (pinfunction "2_2") (pintype "passive"))
      (node (ref "S2") (pin "A") (pinfunction "COM_A") (pintype "passive"))
      (node (ref "S2") (pin "B") (pinfunction "COM_B") (pintype "passive"))
    )
    (net (code "30") (name "Net-(R5-Pad2)") (class "Default")
      (node (ref "R5") (pin "2") (pinfunction "2_2") (pintype "passive"))
      (node (ref "RED_LED") (pin "C") (pinfunction "C_C") (pintype "passive"))
    )
    (net (code "31") (name "Net-(R10-Pad2)") (class "Default")
      (node (ref "R10") (pin "2") (pinfunction "2_2") (pintype "passive"))
      (node (ref "R29") (pin "1") (pinfunction "1_1") (pintype "passive"))
      (node (ref "R9") (pin "1") (pinfunction "1_1") (pintype "passive"))
    )
    (net (code "32") (name "Net-(U1-PA1)") (class "Default")
      (node (ref "R18") (pin "2") (pinfunction "2_2") (pintype "passive"))
      (node (ref "U1") (pin "11") (pinfunction "PA1_11") (pintype "bidirectional"))
    )
    (net (code "33") (name "Net-(U2-SW)") (class "Default")
      (node (ref "L1") (pin "2") (pinfunction "2_2") (pintype "bidirectional"))
      (node (ref "R15") (pin "2") (pinfunction "2_2") (pintype "passive"))
      (node (ref "SCHOTTKYDIODE0805") (pin "1") (pinfunction "1_1") (pintype "passive"))
      (node (ref "U2") (pin "1") (pinfunction "SW_1") (pintype "input"))
    )
    (net (code "34") (name "Net-(U2-VOUT)") (class "Default")
      (node (ref "C15") (pin "2") (pinfunction "2_2") (pintype "passive"))
      (node (ref "C17") (pin "1") (pinfunction "1_1") (pintype "passive"))
      (node (ref "R16") (pin "1") (pinfunction "1_1") (pintype "passive"))
      (node (ref "SCHOTTKYDIODE0805") (pin "2") (pinfunction "2_2") (pintype "passive"))
      (node (ref "U2") (pin "4") (pinfunction "VOUT_4") (pintype "output"))
    )
    (net (code "35") (name "Net-(U4-FIN)") (class "Default")
      (node (ref "D8") (pin "C") (pinfunction "C_C") (pintype "passive"))
      (node (ref "U4") (pin "3") (pinfunction "FIN_3") (pintype "passive"))
    )
    (net (code "36") (name "Net-(U4-RIN)") (class "Default")
      (node (ref "D9") (pin "C") (pinfunction "C_C") (pintype "passive"))
      (node (ref "U4") (pin "5") (pinfunction "RIN_5") (pintype "passive"))
    )
    (net (code "37") (name "Net-(USB-B-D+)") (class "Default")
      (node (ref "R25") (pin "2") (pinfunction "2_2") (pintype "passive"))
      (node (ref "USB-B") (pin "3") (pinfunction "D+_3") (pintype "bidirectional"))
    )
    (net (code "38") (name "Net-(USB-B-D-)") (class "Default")
      (node (ref "R26") (pin "2") (pinfunction "2_2") (pintype "passive"))
      (node (ref "USB-B") (pin "2") (pinfunction "D-_2") (pintype "bidirectional"))
    )
    (net (code "39") (name "OSC32IN") (class "Default")
      (node (ref "C10") (pin "2") (pinfunction "2_2") (pintype "passive"))
      (node (ref "Q1") (pin "2") (pinfunction "2_2") (pintype "passive"))
      (node (ref "R37") (pin "2") (pinfunction "2_2") (pintype "passive"))
      (node (ref "U1") (pin "3") (pinfunction "PC14-OSC32_IN_3") (pintype "bidirectional"))
    )
    (net (code "40") (name "OSC32OUT") (class "Default")
      (node (ref "C11") (pin "2") (pinfunction "2_2") (pintype "passive"))
      (node (ref "Q1") (pin "1") (pinfunction "1_1") (pintype "passive"))
      (node (ref "R37") (pin "1") (pinfunction "1_1") (pintype "passive"))
      (node (ref "U1") (pin "4") (pinfunction "PC15-OSC32_OUT_4") (pintype "bidirectional"))
    )
    (net (code "41") (name "OSCIN") (class "Default")
      (node (ref "C8") (pin "2") (pinfunction "2_2") (pintype "passive"))
      (node (ref "R12") (pin "2") (pinfunction "2_2") (pintype "passive"))
      (node (ref "U1") (pin "5") (pinfunction "PD0_OSC_IN_5") (pintype "bidirectional"))
      (node (ref "Y1") (pin "2") (pinfunction "2_2") (pintype "passive"))
    )
    (net (code "42") (name "OSCOUT") (class "Default")
      (node (ref "C9") (pin "2") (pinfunction "2_2") (pintype "passive"))
      (node (ref "R12") (pin "1") (pinfunction "1_1") (pintype "passive"))
      (node (ref "U1") (pin "6") (pinfunction "PD1_OSC_OUT_6") (pintype "bidirectional"))
      (node (ref "Y1") (pin "1") (pinfunction "1_1") (pintype "passive"))
    )
    (net (code "43") (name "PAD") (class "Default")
      (node (ref "U4") (pin "8") (pinfunction "EPAD_8") (pintype "passive"))
    )
    (net (code "44") (name "PC13") (class "Default")
      (node (ref "RED_LED") (pin "A") (pinfunction "A_A") (pintype "passive"))
      (node (ref "U1") (pin "2") (pinfunction "PC13-TAMPER-RTC_2") (pintype "bidirectional"))
    )
    (net (code "45") (name "RESET") (class "Default")
      (node (ref "C2") (pin "1") (pinfunction "1_1") (pintype "passive"))
      (node (ref "R2") (pin "1") (pinfunction "1_1") (pintype "passive"))
      (node (ref "RESET") (pin "C") (pinfunction "NO_C") (pintype "passive"))
      (node (ref "RESET") (pin "D") (pinfunction "NO_D") (pintype "passive"))
      (node (ref "U1") (pin "7") (pinfunction "NRST_7") (pintype "input"))
    )
    (net (code "46") (name "SIGNAL_IN") (class "Default")
      (node (ref "AUDIO_JACK") (pin "2") (pinfunction "RING_1_2") (pintype "passive"))
      (node (ref "AUDIO_JACK") (pin "5") (pinfunction "TIP_2_5") (pintype "passive"))
      (node (ref "IC4") (pin "10") (pinfunction "+IN3_10") (pintype "passive"))
    )
    (net (code "47") (name "SIGNAL_OPAMP") (class "Default")
      (node (ref "IC4") (pin "8") (pinfunction "OUT3_8") (pintype "passive"))
      (node (ref "R18") (pin "1") (pinfunction "1_1") (pintype "passive"))
      (node (ref "R27") (pin "1") (pinfunction "1_1") (pintype "passive"))
    )
    (net (code "48") (name "SWDCLK") (class "Default")
      (node (ref "ST_LINK") (pin "2") (pinfunction "2_2") (pintype "passive"))
      (node (ref "U1") (pin "37") (pinfunction "PA14_37") (pintype "bidirectional"))
    )
    (net (code "49") (name "SWDIO") (class "Default")
      (node (ref "ST_LINK") (pin "3") (pinfunction "3_3") (pintype "passive"))
      (node (ref "U1") (pin "34") (pinfunction "PA13_34") (pintype "bidirectional"))
    )
    (net (code "50") (name "USB+") (class "Default")
      (node (ref "D4") (pin "2") (pinfunction "2_2") (pintype "passive"))
      (node (ref "R13") (pin "1") (pinfunction "1_1") (pintype "passive"))
      (node (ref "R25") (pin "1") (pinfunction "1_1") (pintype "passive"))
      (node (ref "U1") (pin "33") (pinfunction "PA12_33") (pintype "bidirectional"))
    )
    (net (code "51") (name "USB-") (class "Default")
      (node (ref "D3") (pin "2") (pinfunction "2_2") (pintype "passive"))
      (node (ref "R26") (pin "1") (pinfunction "1_1") (pintype "passive"))
      (node (ref "U1") (pin "32") (pinfunction "PA11_32") (pintype "bidirectional"))
    )
    (net (code "52") (name "VBAT") (class "Default")
      (node (ref "BATTERIE") (pin "2") (pinfunction "S_2") (pintype "passive"))
      (node (ref "C4") (pin "+") (pinfunction "+_+") (pintype "passive"))
      (node (ref "IC1") (pin "3") (pinfunction "BAT_3") (pintype "bidirectional"))
      (node (ref "Q3") (pin "2") (pinfunction "S_2") (pintype "passive"))
      (node (ref "R9") (pin "2") (pinfunction "2_2") (pintype "passive"))
      (node (ref "U4") (pin "1") (pinfunction "VREF_1") (pintype "power_in"))
      (node (ref "U4") (pin "7") (pinfunction "VCC_7") (pintype "power_in"))
    )
    (net (code "53") (name "VBUS") (class "Default")
      (node (ref "C12") (pin "1") (pinfunction "1_1") (pintype "passive"))
      (node (ref "D1") (pin "2") (pinfunction "A_2") (pintype "passive"))
      (node (ref "D2") (pin "2") (pinfunction "2_2") (pintype "passive"))
      (node (ref "IC1") (pin "4") (pinfunction "VCC_4") (pintype "bidirectional"))
      (node (ref "Q3") (pin "1") (pinfunction "G_1") (pintype "passive"))
      (node (ref "R11") (pin "2") (pinfunction "2_2") (pintype "passive"))
      (node (ref "R7") (pin "1") (pinfunction "1_1") (pintype "passive"))
      (node (ref "R8") (pin "1") (pinfunction "1_1") (pintype "passive"))
      (node (ref "USB-B") (pin "1") (pinfunction "VCC_1") (pintype "power_in"))
    )
    (net (code "54") (name "VIN") (class "Default")
      (node (ref "C16") (pin "1") (pinfunction "1_1") (pintype "passive"))
      (node (ref "D1") (pin "1") (pinfunction "C_1") (pintype "passive"))
      (node (ref "L1") (pin "1") (pinfunction "1_1") (pintype "bidirectional"))
      (node (ref "Q3") (pin "3") (pinfunction "D_3") (pintype "passive"))
    )
    (net (code "55") (name "unconnected-(AUDIO_JACK-RING_2-Pad3)") (class "Default")
      (node (ref "AUDIO_JACK") (pin "3") (pinfunction "RING_2_3") (pintype "passive"))
    )
    (net (code "56") (name "unconnected-(AUDIO_JACK-TIP_1-Pad4)") (class "Default")
      (node (ref "AUDIO_JACK") (pin "4") (pinfunction "TIP_1_4") (pintype "passive"))
    )
    (net (code "57") (name "unconnected-(IC4-+IN1-Pad3)") (class "Default")
      (node (ref "IC4") (pin "3") (pinfunction "+IN1_3") (pintype "bidirectional"))
    )
    (net (code "58") (name "unconnected-(IC4-+IN2-Pad5)") (class "Default")
      (node (ref "IC4") (pin "5") (pinfunction "+IN2_5") (pintype "passive"))
    )
    (net (code "59") (name "unconnected-(IC4-+IN4-Pad12)") (class "Default")
      (node (ref "IC4") (pin "12") (pinfunction "+IN4_12") (pintype "bidirectional"))
    )
    (net (code "60") (name "unconnected-(IC4--IN1-Pad2)") (class "Default")
      (node (ref "IC4") (pin "2") (pinfunction "-IN1_2") (pintype "input"))
    )
    (net (code "61") (name "unconnected-(IC4--IN2-Pad6)") (class "Default")
      (node (ref "IC4") (pin "6") (pinfunction "-IN2_6") (pintype "passive"))
    )
    (net (code "62") (name "unconnected-(IC4--IN4-Pad13)") (class "Default")
      (node (ref "IC4") (pin "13") (pinfunction "-IN4_13") (pintype "bidirectional"))
    )
    (net (code "63") (name "unconnected-(IC4-OUT1-Pad1)") (class "Default")
      (node (ref "IC4") (pin "1") (pinfunction "OUT1_1") (pintype "input"))
    )
    (net (code "64") (name "unconnected-(IC4-OUT2-Pad7)") (class "Default")
      (node (ref "IC4") (pin "7") (pinfunction "OUT2_7") (pintype "passive"))
    )
    (net (code "65") (name "unconnected-(IC4-OUT4-Pad14)") (class "Default")
      (node (ref "IC4") (pin "14") (pinfunction "OUT4_14") (pintype "output"))
    )
    (net (code "66") (name "unconnected-(U1-PA0_WKUP-Pad10)") (class "Default")
      (node (ref "U1") (pin "10") (pinfunction "PA0_WKUP_10") (pintype "bidirectional"))
    )
    (net (code "67") (name "unconnected-(U1-PA2-Pad12)") (class "Default")
      (node (ref "U1") (pin "12") (pinfunction "PA2_12") (pintype "bidirectional"))
    )
    (net (code "68") (name "unconnected-(U1-PA3-Pad13)") (class "Default")
      (node (ref "U1") (pin "13") (pinfunction "PA3_13") (pintype "bidirectional"))
    )
    (net (code "69") (name "unconnected-(U1-PA4-Pad14)") (class "Default")
      (node (ref "U1") (pin "14") (pinfunction "PA4_14") (pintype "bidirectional"))
    )
    (net (code "70") (name "unconnected-(U1-PA5-Pad15)") (class "Default")
      (node (ref "U1") (pin "15") (pinfunction "PA5_15") (pintype "bidirectional"))
    )
    (net (code "71") (name "unconnected-(U1-PA7-Pad17)") (class "Default")
      (node (ref "U1") (pin "17") (pinfunction "PA7_17") (pintype "bidirectional"))
    )
    (net (code "72") (name "unconnected-(U1-PA15-Pad38)") (class "Default")
      (node (ref "U1") (pin "38") (pinfunction "PA15_38") (pintype "bidirectional"))
    )
    (net (code "73") (name "unconnected-(U1-PB2-Pad20)") (class "Default")
      (node (ref "U1") (pin "20") (pinfunction "PB2_20") (pintype "bidirectional"))
    )
    (net (code "74") (name "unconnected-(U1-PB3-Pad39)") (class "Default")
      (node (ref "U1") (pin "39") (pinfunction "PB3_39") (pintype "bidirectional"))
    )
    (net (code "75") (name "unconnected-(U1-PB4-Pad40)") (class "Default")
      (node (ref "U1") (pin "40") (pinfunction "PB4_40") (pintype "bidirectional"))
    )
    (net (code "76") (name "unconnected-(U1-PB5-Pad41)") (class "Default")
      (node (ref "U1") (pin "41") (pinfunction "PB5_41") (pintype "bidirectional"))
    )
    (net (code "77") (name "unconnected-(U1-PB8-Pad45)") (class "Default")
      (node (ref "U1") (pin "45") (pinfunction "PB8_45") (pintype "bidirectional"))
    )
    (net (code "78") (name "unconnected-(U1-PB9-Pad46)") (class "Default")
      (node (ref "U1") (pin "46") (pinfunction "PB9_46") (pintype "bidirectional"))
    )
    (net (code "79") (name "unconnected-(U1-PB10-Pad21)") (class "Default")
      (node (ref "U1") (pin "21") (pinfunction "PB10_21") (pintype "bidirectional"))
    )
    (net (code "80") (name "unconnected-(U1-PB11-Pad22)") (class "Default")
      (node (ref "U1") (pin "22") (pinfunction "PB11_22") (pintype "bidirectional"))
    )
    (net (code "81") (name "unconnected-(U1-PB12-Pad25)") (class "Default")
      (node (ref "U1") (pin "25") (pinfunction "PB12_25") (pintype "bidirectional"))
    )
  )
)
